# 5DPD8_v1_0_OS_Sheet3.net
KiCad netlist of a schematic drawn in Altium Designer
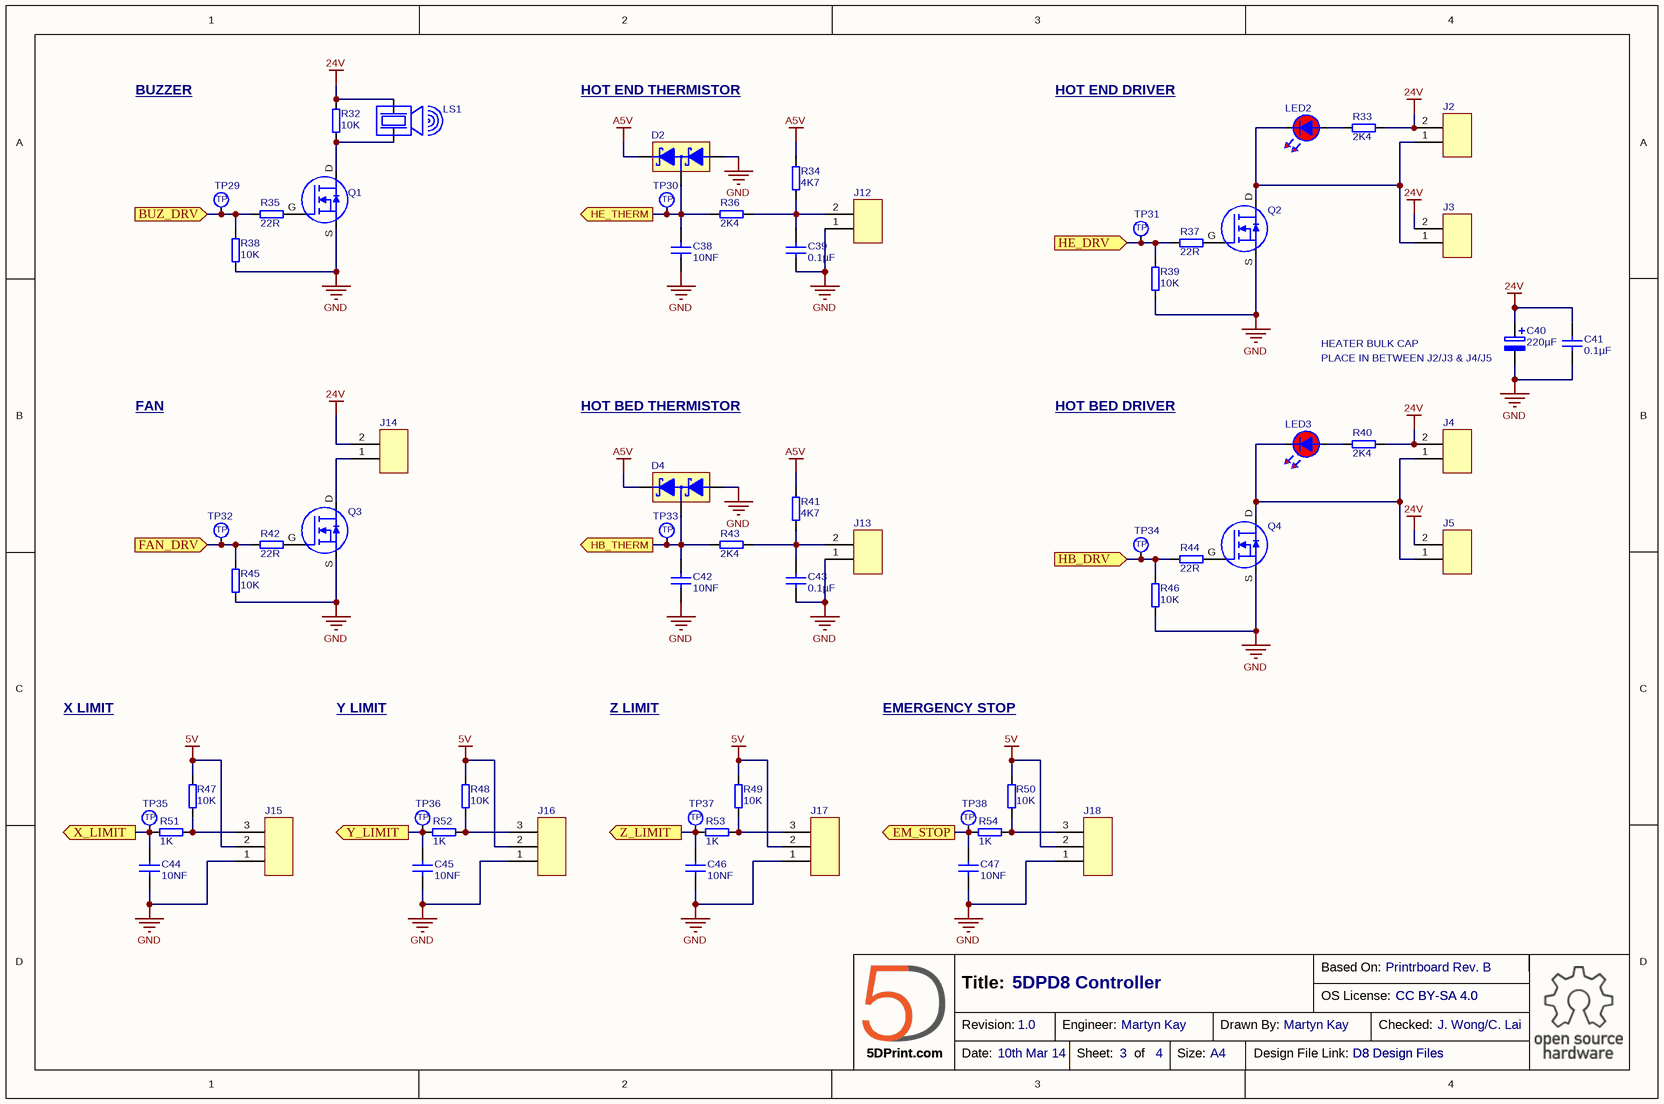
[diagram p0: 5DPD8_v1.0_OS_Sheet3.SchDoc]

(export (version "E")
  (design (tool "Eeschema 10.0.6"))
  (components
    (comp (ref "C38")
      (value "10NF")
      (footprint "CAPC0603(1608)100_N")
      (description "CAP CER 10000PF 50V 10% X7R 0603")
      (fields
        (field (name "MANUFACTURER") "Yageo")
        (field (name "MANUFACTURERPARTNUMBER") "CC0603KPX7R9BB103")
      )
      (libsource (lib "5DPD8") (part "C0603-10NF-50V-10%-X7R"))
    )
    (comp (ref "C39")
      (value "0.1µF")
      (footprint "CAPC0603(1608)100_N")
      (description "CAP CER 0.1UF 50V 10% X7R 0603")
      (fields
        (field (name "MANUFACTURER") "Yageo")
        (field (name "MANUFACTURERPARTNUMBER") "CC0603KRX7R9BB104")
      )
      (libsource (lib "5DPD8") (part "C0603-0.1UF-50V-10%-X7R"))
    )
    (comp (ref "C40")
      (value "220µF")
      (footprint "CAPRAD8X11.5")
      (description "CAP ALUM 220UF 35V 20% RADIAL")
      (fields
        (field (name "MANUFACTURER") "Rubycon")
        (field (name "MANUFACTURERPARTNUMBER") "35ZLH220MEFC8X11.5")
      )
      (libsource (lib "5DPD8") (part "CAP_RAD-ALU-220UF-35V-20%"))
    )
    (comp (ref "C41")
      (value "0.1µF")
      (footprint "CAPC0603(1608)100_N")
      (description "CAP CER 0.1UF 50V 10% X7R 0603")
      (fields
        (field (name "MANUFACTURER") "Yageo")
        (field (name "MANUFACTURERPARTNUMBER") "CC0603KRX7R9BB104")
      )
      (libsource (lib "5DPD8") (part "C0603-0.1UF-50V-10%-X7R"))
    )
    (comp (ref "C42")
      (value "10NF")
      (footprint "CAPC0603(1608)100_N")
      (description "CAP CER 10000PF 50V 10% X7R 0603")
      (fields
        (field (name "MANUFACTURER") "Yageo")
        (field (name "MANUFACTURERPARTNUMBER") "CC0603KPX7R9BB103")
      )
      (libsource (lib "5DPD8") (part "C0603-10NF-50V-10%-X7R"))
    )
    (comp (ref "C43")
      (value "0.1µF")
      (footprint "CAPC0603(1608)100_N")
      (description "CAP CER 0.1UF 50V 10% X7R 0603")
      (fields
        (field (name "MANUFACTURER") "Yageo")
        (field (name "MANUFACTURERPARTNUMBER") "CC0603KRX7R9BB104")
      )
      (libsource (lib "5DPD8") (part "C0603-0.1UF-50V-10%-X7R"))
    )
    (comp (ref "C44")
      (value "10NF")
      (footprint "CAPC0603(1608)100_N")
      (description "CAP CER 10000PF 50V 10% X7R 0603")
      (fields
        (field (name "MANUFACTURER") "Yageo")
        (field (name "MANUFACTURERPARTNUMBER") "CC0603KPX7R9BB103")
      )
      (libsource (lib "5DPD8") (part "C0603-10NF-50V-10%-X7R"))
    )
    (comp (ref "C45")
      (value "10NF")
      (footprint "CAPC0603(1608)100_N")
      (description "CAP CER 10000PF 50V 10% X7R 0603")
      (fields
        (field (name "MANUFACTURER") "Yageo")
        (field (name "MANUFACTURERPARTNUMBER") "CC0603KPX7R9BB103")
      )
      (libsource (lib "5DPD8") (part "C0603-10NF-50V-10%-X7R"))
    )
    (comp (ref "C46")
      (value "10NF")
      (footprint "CAPC0603(1608)100_N")
      (description "CAP CER 10000PF 50V 10% X7R 0603")
      (fields
        (field (name "MANUFACTURER") "Yageo")
        (field (name "MANUFACTURERPARTNUMBER") "CC0603KPX7R9BB103")
      )
      (libsource (lib "5DPD8") (part "C0603-10NF-50V-10%-X7R"))
    )
    (comp (ref "C47")
      (value "10NF")
      (footprint "CAPC0603(1608)100_N")
      (description "CAP CER 10000PF 50V 10% X7R 0603")
      (fields
        (field (name "MANUFACTURER") "Yageo")
        (field (name "MANUFACTURERPARTNUMBER") "CC0603KPX7R9BB103")
      )
      (libsource (lib "5DPD8") (part "C0603-10NF-50V-10%-X7R"))
    )
    (comp (ref "D2")
      (value "BAT54S,215")
      (footprint "SOT95P237X112-3N")
      (description "DIODE SCHOTTKY 30V 200MA TO236AB")
      (fields (field (name "MANUFACTURER") "NXP Semiconductors"))
      (libsource (lib "5DPD8") (part "DIO_BAT54S,215"))
    )
    (comp (ref "D4")
      (value "BAT54S,215")
      (footprint "SOT95P237X112-3N")
      (description "DIODE SCHOTTKY 30V 200MA TO236AB")
      (fields (field (name "MANUFACTURER") "NXP Semiconductors"))
      (libsource (lib "5DPD8") (part "DIO_BAT54S,215"))
    )
    (comp (ref "J2")
      (value "0039281023")
      (footprint "MOLEX_39-28-1023")
      (description "CONN HEADER 2POS 4.2MM VERT TIN")
      (fields (field (name "MANUFACTURER") "Molex Inc"))
      (libsource (lib "5DPD8") (part "CON_MLX_39-28-1023"))
    )
    (comp (ref "J3")
      (value "0039281023")
      (footprint "MOLEX_39-28-1023")
      (description "CONN HEADER 2POS 4.2MM VERT TIN")
      (fields (field (name "MANUFACTURER") "Molex Inc"))
      (libsource (lib "5DPD8") (part "CON_MLX_39-28-1023"))
    )
    (comp (ref "J4")
      (value "0039281023")
      (footprint "MOLEX_39-28-1023")
      (description "CONN HEADER 2POS 4.2MM VERT TIN")
      (fields (field (name "MANUFACTURER") "Molex Inc"))
      (libsource (lib "5DPD8") (part "CON_MLX_39-28-1023"))
    )
    (comp (ref "J5")
      (value "0039281023")
      (footprint "MOLEX_39-28-1023")
      (description "CONN HEADER 2POS 4.2MM VERT TIN")
      (fields (field (name "MANUFACTURER") "Molex Inc"))
      (libsource (lib "5DPD8") (part "CON_MLX_39-28-1023"))
    )
    (comp (ref "J12")
      (value "0022272021")
      (footprint "MOLEX_22-27-2021")
      (description "CONN HEADER 2POS .100 VERT TIN")
      (fields (field (name "MANUFACTURER") "Molex Inc"))
      (libsource (lib "5DPD8") (part "CON_MLX_22-27-2021"))
    )
    (comp (ref "J13")
      (value "0022272021")
      (footprint "MOLEX_22-27-2021")
      (description "CONN HEADER 2POS .100 VERT TIN")
      (fields (field (name "MANUFACTURER") "Molex Inc"))
      (libsource (lib "5DPD8") (part "CON_MLX_22-27-2021"))
    )
    (comp (ref "J14")
      (value "0022272021")
      (footprint "MOLEX_22-27-2021")
      (description "CONN HEADER 2POS .100 VERT TIN")
      (fields (field (name "MANUFACTURER") "Molex Inc"))
      (libsource (lib "5DPD8") (part "CON_MLX_22-27-2021"))
    )
    (comp (ref "J15")
      (value "0022272031")
      (footprint "MOLEX_22-27-2031")
      (description "CONN HEADER 3POS .100 VERT TIN")
      (fields (field (name "MANUFACTURER") "Molex Inc"))
      (libsource (lib "5DPD8") (part "CON_MLX_22-27-2031"))
    )
    (comp (ref "J16")
      (value "0022272031")
      (footprint "MOLEX_22-27-2031")
      (description "CONN HEADER 3POS .100 VERT TIN")
      (fields (field (name "MANUFACTURER") "Molex Inc"))
      (libsource (lib "5DPD8") (part "CON_MLX_22-27-2031"))
    )
    (comp (ref "J17")
      (value "0022272031")
      (footprint "MOLEX_22-27-2031")
      (description "CONN HEADER 3POS .100 VERT TIN")
      (fields (field (name "MANUFACTURER") "Molex Inc"))
      (libsource (lib "5DPD8") (part "CON_MLX_22-27-2031"))
    )
    (comp (ref "J18")
      (value "0022272031")
      (footprint "MOLEX_22-27-2031")
      (description "CONN HEADER 3POS .100 VERT TIN")
      (fields (field (name "MANUFACTURER") "Molex Inc"))
      (libsource (lib "5DPD8") (part "CON_MLX_22-27-2031"))
    )
    (comp (ref "LED2")
      (value "HSMH-C190")
      (footprint "LEDC0603(1608)_N-RED")
      (description "LED 660NM RED DIFF 0603 SMD")
      (fields (field (name "MANUFACTURER") "Avago Technologies US Inc."))
      (libsource (lib "5DPD8") (part "LED_HSMH-C190"))
    )
    (comp (ref "LED3")
      (value "HSMH-C190")
      (footprint "LEDC0603(1608)_N-RED")
      (description "LED 660NM RED DIFF 0603 SMD")
      (fields (field (name "MANUFACTURER") "Avago Technologies US Inc."))
      (libsource (lib "5DPD8") (part "LED_HSMH-C190"))
    )
    (comp (ref "LS1")
      (value "PS1740P02E")
      (footprint "PS17")
      (description "BUZZER PIEZO 4KHZ 17MM PC MOUNT")
      (fields (field (name "MANUFACTURER") "TDK Corporation"))
      (libsource (lib "5DPD8") (part "LS_PS1740P02E"))
    )
    (comp (ref "Q1")
      (value "2N7002,215")
      (footprint "SOT95P237X112-3N-GSD")
      (description "MOSFET N-CH 60V 300MA SOT-23")
      (fields (field (name "MANUFACTURER") "NXP Semiconductors"))
      (libsource (lib "5DPD8") (part "FET_2N7002,215"))
    )
    (comp (ref "Q2")
      (value "PSMN9R5-30YLC,115")
      (footprint "SOT669(LFPAK56)")
      (description "MOSFET N-CH 30V 44A LL LFPAK")
      (fields (field (name "MANUFACTURER") "NXP Semiconductors"))
      (libsource (lib "5DPD8") (part "FET_PSMN9R5-30YLC,115"))
    )
    (comp (ref "Q3")
      (value "IRLML2060TRPBF")
      (footprint "SOT95P237X112-3N-GSD")
      (description "MOSFET N-CH 60V 1.2A SOT23-3")
      (fields (field (name "MANUFACTURER") "International Rectifier"))
      (libsource (lib "5DPD8") (part "FET_IRLML2060TRPBF"))
    )
    (comp (ref "Q4")
      (value "PSMN9R5-30YLC,115")
      (footprint "SOT669(LFPAK56)")
      (description "MOSFET N-CH 30V 44A LL LFPAK")
      (fields (field (name "MANUFACTURER") "NXP Semiconductors"))
      (libsource (lib "5DPD8") (part "FET_PSMN9R5-30YLC,115"))
    )
    (comp (ref "R32")
      (value "10K")
      (footprint "RESC0603(1608)_N")
      (description "RES 10K OHM 1/10W 5% 0603 SMD")
      (fields (field (name "MANUFACTURER") "Yageo") (field (name "MANUFACTURERPARTNUMBER") "RC0603JR-0710KL"))
      (libsource (lib "5DPD8") (part "R0603-10K-0.1W-5%"))
    )
    (comp (ref "R33")
      (value "2K4")
      (footprint "RESC0603(1608)_N")
      (description "RES 2.4K OHM 1/4W 5% 0603 SMD")
      (fields
        (field (name "MANUFACTURER") "Rohm Semiconductor")
        (field (name "MANUFACTURERPARTNUMBER") "ESR03EZPJ242")
      )
      (libsource (lib "5DPD8") (part "R0603-2K4-0.25W-5%"))
    )
    (comp (ref "R34")
      (value "4K7")
      (footprint "RESC0603(1608)_N")
      (description "RES 4.70K OHM 1/10W 1% 0603 SMD")
      (fields (field (name "MANUFACTURER") "Yageo") (field (name "MANUFACTURERPARTNUMBER") "RC0603FR-074K7L"))
      (libsource (lib "5DPD8") (part "R0603-4K7-0.1W-1%"))
    )
    (comp (ref "R35")
      (value "22R")
      (footprint "RESC0603(1608)_N")
      (description "RES 22.0 OHM 1/10W 1% 0603 SMD")
      (fields (field (name "MANUFACTURER") "Yageo") (field (name "MANUFACTURERPARTNUMBER") "RC0603FR-0722RL"))
      (libsource (lib "5DPD8") (part "R0603-22R-0.1W-1%"))
    )
    (comp (ref "R36")
      (value "2K4")
      (footprint "RESC0603(1608)_N")
      (description "RES 2.4K OHM 1/4W 5% 0603 SMD")
      (fields
        (field (name "MANUFACTURER") "Rohm Semiconductor")
        (field (name "MANUFACTURERPARTNUMBER") "ESR03EZPJ242")
      )
      (libsource (lib "5DPD8") (part "R0603-2K4-0.25W-5%"))
    )
    (comp (ref "R37")
      (value "22R")
      (footprint "RESC0603(1608)_N")
      (description "RES 22.0 OHM 1/10W 1% 0603 SMD")
      (fields (field (name "MANUFACTURER") "Yageo") (field (name "MANUFACTURERPARTNUMBER") "RC0603FR-0722RL"))
      (libsource (lib "5DPD8") (part "R0603-22R-0.1W-1%"))
    )
    (comp (ref "R38")
      (value "10K")
      (footprint "RESC0603(1608)_N")
      (description "RES 10K OHM 1/10W 5% 0603 SMD")
      (fields (field (name "MANUFACTURER") "Yageo") (field (name "MANUFACTURERPARTNUMBER") "RC0603JR-0710KL"))
      (libsource (lib "5DPD8") (part "R0603-10K-0.1W-5%"))
    )
    (comp (ref "R39")
      (value "10K")
      (footprint "RESC0603(1608)_N")
      (description "RES 10K OHM 1/10W 5% 0603 SMD")
      (fields (field (name "MANUFACTURER") "Yageo") (field (name "MANUFACTURERPARTNUMBER") "RC0603JR-0710KL"))
      (libsource (lib "5DPD8") (part "R0603-10K-0.1W-5%"))
    )
    (comp (ref "R40")
      (value "2K4")
      (footprint "RESC0603(1608)_N")
      (description "RES 2.4K OHM 1/4W 5% 0603 SMD")
      (fields
        (field (name "MANUFACTURER") "Rohm Semiconductor")
        (field (name "MANUFACTURERPARTNUMBER") "ESR03EZPJ242")
      )
      (libsource (lib "5DPD8") (part "R0603-2K4-0.25W-5%"))
    )
    (comp (ref "R41")
      (value "4K7")
      (footprint "RESC0603(1608)_N")
      (description "RES 4.70K OHM 1/10W 1% 0603 SMD")
      (fields (field (name "MANUFACTURER") "Yageo") (field (name "MANUFACTURERPARTNUMBER") "RC0603FR-074K7L"))
      (libsource (lib "5DPD8") (part "R0603-4K7-0.1W-1%"))
    )
    (comp (ref "R42")
      (value "22R")
      (footprint "RESC0603(1608)_N")
      (description "RES 22.0 OHM 1/10W 1% 0603 SMD")
      (fields (field (name "MANUFACTURER") "Yageo") (field (name "MANUFACTURERPARTNUMBER") "RC0603FR-0722RL"))
      (libsource (lib "5DPD8") (part "R0603-22R-0.1W-1%"))
    )
    (comp (ref "R43")
      (value "2K4")
      (footprint "RESC0603(1608)_N")
      (description "RES 2.4K OHM 1/4W 5% 0603 SMD")
      (fields
        (field (name "MANUFACTURER") "Rohm Semiconductor")
        (field (name "MANUFACTURERPARTNUMBER") "ESR03EZPJ242")
      )
      (libsource (lib "5DPD8") (part "R0603-2K4-0.25W-5%"))
    )
    (comp (ref "R44")
      (value "22R")
      (footprint "RESC0603(1608)_N")
      (description "RES 22.0 OHM 1/10W 1% 0603 SMD")
      (fields (field (name "MANUFACTURER") "Yageo") (field (name "MANUFACTURERPARTNUMBER") "RC0603FR-0722RL"))
      (libsource (lib "5DPD8") (part "R0603-22R-0.1W-1%"))
    )
    (comp (ref "R45")
      (value "10K")
      (footprint "RESC0603(1608)_N")
      (description "RES 10K OHM 1/10W 5% 0603 SMD")
      (fields (field (name "MANUFACTURER") "Yageo") (field (name "MANUFACTURERPARTNUMBER") "RC0603JR-0710KL"))
      (libsource (lib "5DPD8") (part "R0603-10K-0.1W-5%"))
    )
    (comp (ref "R46")
      (value "10K")
      (footprint "RESC0603(1608)_N")
      (description "RES 10K OHM 1/10W 5% 0603 SMD")
      (fields (field (name "MANUFACTURER") "Yageo") (field (name "MANUFACTURERPARTNUMBER") "RC0603JR-0710KL"))
      (libsource (lib "5DPD8") (part "R0603-10K-0.1W-5%"))
    )
    (comp (ref "R47")
      (value "10K")
      (footprint "RESC0603(1608)_N")
      (description "RES 10K OHM 1/10W 5% 0603 SMD")
      (fields (field (name "MANUFACTURER") "Yageo") (field (name "MANUFACTURERPARTNUMBER") "RC0603JR-0710KL"))
      (libsource (lib "5DPD8") (part "R0603-10K-0.1W-5%"))
    )
    (comp (ref "R48")
      (value "10K")
      (footprint "RESC0603(1608)_N")
      (description "RES 10K OHM 1/10W 5% 0603 SMD")
      (fields (field (name "MANUFACTURER") "Yageo") (field (name "MANUFACTURERPARTNUMBER") "RC0603JR-0710KL"))
      (libsource (lib "5DPD8") (part "R0603-10K-0.1W-5%"))
    )
    (comp (ref "R49")
      (value "10K")
      (footprint "RESC0603(1608)_N")
      (description "RES 10K OHM 1/10W 5% 0603 SMD")
      (fields (field (name "MANUFACTURER") "Yageo") (field (name "MANUFACTURERPARTNUMBER") "RC0603JR-0710KL"))
      (libsource (lib "5DPD8") (part "R0603-10K-0.1W-5%"))
    )
    (comp (ref "R50")
      (value "10K")
      (footprint "RESC0603(1608)_N")
      (description "RES 10K OHM 1/10W 5% 0603 SMD")
      (fields (field (name "MANUFACTURER") "Yageo") (field (name "MANUFACTURERPARTNUMBER") "RC0603JR-0710KL"))
      (libsource (lib "5DPD8") (part "R0603-10K-0.1W-5%"))
    )
    (comp (ref "R51")
      (value "1K")
      (footprint "RESC0603(1608)_N")
      (description "RES 1.00K OHM 1/10W 1% 0603 SMD")
      (fields (field (name "MANUFACTURER") "Yageo") (field (name "MANUFACTURERPARTNUMBER") "RC0603FR-071KL"))
      (libsource (lib "5DPD8") (part "R0603-1K-0.1W-1%"))
    )
    (comp (ref "R52")
      (value "1K")
      (footprint "RESC0603(1608)_N")
      (description "RES 1.00K OHM 1/10W 1% 0603 SMD")
      (fields (field (name "MANUFACTURER") "Yageo") (field (name "MANUFACTURERPARTNUMBER") "RC0603FR-071KL"))
      (libsource (lib "5DPD8") (part "R0603-1K-0.1W-1%"))
    )
    (comp (ref "R53")
      (value "1K")
      (footprint "RESC0603(1608)_N")
      (description "RES 1.00K OHM 1/10W 1% 0603 SMD")
      (fields (field (name "MANUFACTURER") "Yageo") (field (name "MANUFACTURERPARTNUMBER") "RC0603FR-071KL"))
      (libsource (lib "5DPD8") (part "R0603-1K-0.1W-1%"))
    )
    (comp (ref "R54")
      (value "1K")
      (footprint "RESC0603(1608)_N")
      (description "RES 1.00K OHM 1/10W 1% 0603 SMD")
      (fields (field (name "MANUFACTURER") "Yageo") (field (name "MANUFACTURERPARTNUMBER") "RC0603FR-071KL"))
      (libsource (lib "5DPD8") (part "R0603-1K-0.1W-1%"))
    )
    (comp (ref "TP29")
      (value "TESTPOINT")
      (footprint "TESTPOINT")
      (libsource (lib "5DPD8") (part "TESTPOINT"))
    )
    (comp (ref "TP30")
      (value "TESTPOINT")
      (footprint "TESTPOINT")
      (libsource (lib "5DPD8") (part "TESTPOINT"))
    )
    (comp (ref "TP31")
      (value "TESTPOINT")
      (footprint "TESTPOINT")
      (libsource (lib "5DPD8") (part "TESTPOINT"))
    )
    (comp (ref "TP32")
      (value "TESTPOINT")
      (footprint "TESTPOINT")
      (libsource (lib "5DPD8") (part "TESTPOINT"))
    )
    (comp (ref "TP33")
      (value "TESTPOINT")
      (footprint "TESTPOINT")
      (libsource (lib "5DPD8") (part "TESTPOINT"))
    )
    (comp (ref "TP34")
      (value "TESTPOINT")
      (footprint "TESTPOINT")
      (libsource (lib "5DPD8") (part "TESTPOINT"))
    )
    (comp (ref "TP35")
      (value "TESTPOINT")
      (footprint "TESTPOINT")
      (libsource (lib "5DPD8") (part "TESTPOINT"))
    )
    (comp (ref "TP36")
      (value "TESTPOINT")
      (footprint "TESTPOINT")
      (libsource (lib "5DPD8") (part "TESTPOINT"))
    )
    (comp (ref "TP37")
      (value "TESTPOINT")
      (footprint "TESTPOINT")
      (libsource (lib "5DPD8") (part "TESTPOINT"))
    )
    (comp (ref "TP38")
      (value "TESTPOINT")
      (footprint "TESTPOINT")
      (libsource (lib "5DPD8") (part "TESTPOINT"))
    )
  )
  (nets
    (net (code "1") (name "/BUZ_DRV") (class "Default")
      (node (ref "R35") (pin "1") (pinfunction "1_1") (pintype "passive"))
      (node (ref "R38") (pin "2") (pinfunction "2_2") (pintype "passive"))
      (node (ref "TP29") (pin "1") (pinfunction "1_1") (pintype "passive"))
    )
    (net (code "2") (name "/EM_STOP") (class "Default")
      (node (ref "C47") (pin "2") (pinfunction "2_2") (pintype "passive"))
      (node (ref "R54") (pin "1") (pinfunction "1_1") (pintype "passive"))
      (node (ref "TP38") (pin "1") (pinfunction "1_1") (pintype "passive"))
    )
    (net (code "3") (name "/FAN_DRV") (class "Default")
      (node (ref "R42") (pin "1") (pinfunction "1_1") (pintype "passive"))
      (node (ref "R45") (pin "2") (pinfunction "2_2") (pintype "passive"))
      (node (ref "TP32") (pin "1") (pinfunction "1_1") (pintype "passive"))
    )
    (net (code "4") (name "/HB_DRV") (class "Default")
      (node (ref "R44") (pin "1") (pinfunction "1_1") (pintype "passive"))
      (node (ref "R46") (pin "2") (pinfunction "2_2") (pintype "passive"))
      (node (ref "TP34") (pin "1") (pinfunction "1_1") (pintype "passive"))
    )
    (net (code "5") (name "/HB_THERM") (class "Default")
      (node (ref "C42") (pin "2") (pinfunction "2_2") (pintype "passive"))
      (node (ref "D4") (pin "3") (pinfunction "3_3") (pintype "passive"))
      (node (ref "R43") (pin "1") (pinfunction "1_1") (pintype "passive"))
      (node (ref "TP33") (pin "1") (pinfunction "1_1") (pintype "passive"))
    )
    (net (code "6") (name "/HE_DRV") (class "Default")
      (node (ref "R37") (pin "1") (pinfunction "1_1") (pintype "passive"))
      (node (ref "R39") (pin "2") (pinfunction "2_2") (pintype "passive"))
      (node (ref "TP31") (pin "1") (pinfunction "1_1") (pintype "passive"))
    )
    (net (code "7") (name "/HE_THERM") (class "Default")
      (node (ref "C38") (pin "2") (pinfunction "2_2") (pintype "passive"))
      (node (ref "D2") (pin "3") (pinfunction "3_3") (pintype "passive"))
      (node (ref "R36") (pin "1") (pinfunction "1_1") (pintype "passive"))
      (node (ref "TP30") (pin "1") (pinfunction "1_1") (pintype "passive"))
    )
    (net (code "8") (name "/X_LIMIT") (class "Default")
      (node (ref "C44") (pin "2") (pinfunction "2_2") (pintype "passive"))
      (node (ref "R51") (pin "1") (pinfunction "1_1") (pintype "passive"))
      (node (ref "TP35") (pin "1") (pinfunction "1_1") (pintype "passive"))
    )
    (net (code "9") (name "/Y_LIMIT") (class "Default")
      (node (ref "C45") (pin "2") (pinfunction "2_2") (pintype "passive"))
      (node (ref "R52") (pin "1") (pinfunction "1_1") (pintype "passive"))
      (node (ref "TP36") (pin "1") (pinfunction "1_1") (pintype "passive"))
    )
    (net (code "10") (name "/Z_LIMIT") (class "Default")
      (node (ref "C46") (pin "2") (pinfunction "2_2") (pintype "passive"))
      (node (ref "R53") (pin "1") (pinfunction "1_1") (pintype "passive"))
      (node (ref "TP37") (pin "1") (pinfunction "1_1") (pintype "passive"))
    )
    (net (code "11") (name "5V") (class "Default")
      (node (ref "J15") (pin "2") (pinfunction "2_2") (pintype "passive"))
      (node (ref "J16") (pin "2") (pinfunction "2_2") (pintype "passive"))
      (node (ref "J17") (pin "2") (pinfunction "2_2") (pintype "passive"))
      (node (ref "J18") (pin "2") (pinfunction "2_2") (pintype "passive"))
      (node (ref "R47") (pin "2") (pinfunction "2_2") (pintype "passive"))
      (node (ref "R48") (pin "2") (pinfunction "2_2") (pintype "passive"))
      (node (ref "R49") (pin "2") (pinfunction "2_2") (pintype "passive"))
      (node (ref "R50") (pin "2") (pinfunction "2_2") (pintype "passive"))
    )
    (net (code "12") (name "24V") (class "Default")
      (node (ref "C40") (pin "1") (pinfunction "+_1") (pintype "passive"))
      (node (ref "C41") (pin "2") (pinfunction "2_2") (pintype "passive"))
      (node (ref "J14") (pin "2") (pinfunction "2_2") (pintype "passive"))
      (node (ref "J2") (pin "2") (pinfunction "2_2") (pintype "passive"))
      (node (ref "J3") (pin "2") (pinfunction "2_2") (pintype "passive"))
      (node (ref "J4") (pin "2") (pinfunction "2_2") (pintype "passive"))
      (node (ref "J5") (pin "2") (pinfunction "2_2") (pintype "passive"))
      (node (ref "LS1") (pin "2") (pinfunction "2_2") (pintype "passive"))
      (node (ref "R32") (pin "2") (pinfunction "2_2") (pintype "passive"))
      (node (ref "R33") (pin "2") (pinfunction "2_2") (pintype "passive"))
      (node (ref "R40") (pin "2") (pinfunction "2_2") (pintype "passive"))
    )
    (net (code "13") (name "A5V") (class "Default")
      (node (ref "D2") (pin "2") (pinfunction "2_2") (pintype "passive"))
      (node (ref "D4") (pin "2") (pinfunction "2_2") (pintype "passive"))
      (node (ref "R34") (pin "2") (pinfunction "2_2") (pintype "passive"))
      (node (ref "R41") (pin "2") (pinfunction "2_2") (pintype "passive"))
    )
    (net (code "14") (name "GND") (class "Default")
      (node (ref "C38") (pin "1") (pinfunction "1_1") (pintype "passive"))
      (node (ref "C39") (pin "1") (pinfunction "1_1") (pintype "passive"))
      (node (ref "C40") (pin "2") (pinfunction "-_2") (pintype "passive"))
      (node (ref "C41") (pin "1") (pinfunction "1_1") (pintype "passive"))
      (node (ref "C42") (pin "1") (pinfunction "1_1") (pintype "passive"))
      (node (ref "C43") (pin "1") (pinfunction "1_1") (pintype "passive"))
      (node (ref "C44") (pin "1") (pinfunction "1_1") (pintype "passive"))
      (node (ref "C45") (pin "1") (pinfunction "1_1") (pintype "passive"))
      (node (ref "C46") (pin "1") (pinfunction "1_1") (pintype "passive"))
      (node (ref "C47") (pin "1") (pinfunction "1_1") (pintype "passive"))
      (node (ref "D2") (pin "1") (pinfunction "1_1") (pintype "passive"))
      (node (ref "D4") (pin "1") (pinfunction "1_1") (pintype "passive"))
      (node (ref "J12") (pin "1") (pinfunction "1_1") (pintype "passive"))
      (node (ref "J13") (pin "1") (pinfunction "1_1") (pintype "passive"))
      (node (ref "J15") (pin "1") (pinfunction "1_1") (pintype "passive"))
      (node (ref "J16") (pin "1") (pinfunction "1_1") (pintype "passive"))
      (node (ref "J17") (pin "1") (pinfunction "1_1") (pintype "passive"))
      (node (ref "J18") (pin "1") (pinfunction "1_1") (pintype "passive"))
      (node (ref "Q1") (pin "S") (pinfunction "S_S") (pintype "passive"))
      (node (ref "Q2") (pin "S") (pinfunction "S_S") (pintype "passive"))
      (node (ref "Q3") (pin "S") (pinfunction "S_S") (pintype "passive"))
      (node (ref "Q4") (pin "S") (pinfunction "S_S") (pintype "passive"))
      (node (ref "R38") (pin "1") (pinfunction "1_1") (pintype "passive"))
      (node (ref "R39") (pin "1") (pinfunction "1_1") (pintype "passive"))
      (node (ref "R45") (pin "1") (pinfunction "1_1") (pintype "passive"))
      (node (ref "R46") (pin "1") (pinfunction "1_1") (pintype "passive"))
    )
    (net (code "15") (name "Net-(C39-Pad2)") (class "Default")
      (node (ref "C39") (pin "2") (pinfunction "2_2") (pintype "passive"))
      (node (ref "J12") (pin "2") (pinfunction "2_2") (pintype "passive"))
      (node (ref "R34") (pin "1") (pinfunction "1_1") (pintype "passive"))
      (node (ref "R36") (pin "2") (pinfunction "2_2") (pintype "passive"))
    )
    (net (code "16") (name "Net-(C43-Pad2)") (class "Default")
      (node (ref "C43") (pin "2") (pinfunction "2_2") (pintype "passive"))
      (node (ref "J13") (pin "2") (pinfunction "2_2") (pintype "passive"))
      (node (ref "R41") (pin "1") (pinfunction "1_1") (pintype "passive"))
      (node (ref "R43") (pin "2") (pinfunction "2_2") (pintype "passive"))
    )
    (net (code "17") (name "Net-(J2-Pad1)") (class "Default")
      (node (ref "J2") (pin "1") (pinfunction "1_1") (pintype "passive"))
      (node (ref "J3") (pin "1") (pinfunction "1_1") (pintype "passive"))
      (node (ref "LED2") (pin "K") (pinfunction "K_K") (pintype "passive"))
      (node (ref "Q2") (pin "D") (pinfunction "D_D") (pintype "passive"))
    )
    (net (code "18") (name "Net-(J4-Pad1)") (class "Default")
      (node (ref "J4") (pin "1") (pinfunction "1_1") (pintype "passive"))
      (node (ref "J5") (pin "1") (pinfunction "1_1") (pintype "passive"))
      (node (ref "LED3") (pin "K") (pinfunction "K_K") (pintype "passive"))
      (node (ref "Q4") (pin "D") (pinfunction "D_D") (pintype "passive"))
    )
    (net (code "19") (name "Net-(J14-Pad1)") (class "Default")
      (node (ref "J14") (pin "1") (pinfunction "1_1") (pintype "passive"))
      (node (ref "Q3") (pin "D") (pinfunction "D_D") (pintype "passive"))
    )
    (net (code "20") (name "Net-(J15-Pad3)") (class "Default")
      (node (ref "J15") (pin "3") (pinfunction "3_3") (pintype "passive"))
      (node (ref "R47") (pin "1") (pinfunction "1_1") (pintype "passive"))
      (node (ref "R51") (pin "2") (pinfunction "2_2") (pintype "passive"))
    )
    (net (code "21") (name "Net-(J16-Pad3)") (class "Default")
      (node (ref "J16") (pin "3") (pinfunction "3_3") (pintype "passive"))
      (node (ref "R48") (pin "1") (pinfunction "1_1") (pintype "passive"))
      (node (ref "R52") (pin "2") (pinfunction "2_2") (pintype "passive"))
    )
    (net (code "22") (name "Net-(J17-Pad3)") (class "Default")
      (node (ref "J17") (pin "3") (pinfunction "3_3") (pintype "passive"))
      (node (ref "R49") (pin "1") (pinfunction "1_1") (pintype "passive"))
      (node (ref "R53") (pin "2") (pinfunction "2_2") (pintype "passive"))
    )
    (net (code "23") (name "Net-(J18-Pad3)") (class "Default")
      (node (ref "J18") (pin "3") (pinfunction "3_3") (pintype "passive"))
      (node (ref "R50") (pin "1") (pinfunction "1_1") (pintype "passive"))
      (node (ref "R54") (pin "2") (pinfunction "2_2") (pintype "passive"))
    )
    (net (code "24") (name "Net-(LED2-PadA)") (class "Default")
      (node (ref "LED2") (pin "A") (pinfunction "A_A") (pintype "passive"))
      (node (ref "R33") (pin "1") (pinfunction "1_1") (pintype "passive"))
    )
    (net (code "25") (name "Net-(LED3-PadA)") (class "Default")
      (node (ref "LED3") (pin "A") (pinfunction "A_A") (pintype "passive"))
      (node (ref "R40") (pin "1") (pinfunction "1_1") (pintype "passive"))
    )
    (net (code "26") (name "Net-(LS1-Pad1)") (class "Default")
      (node (ref "LS1") (pin "1") (pinfunction "1_1") (pintype "passive"))
      (node (ref "Q1") (pin "D") (pinfunction "D_D") (pintype "passive"))
      (node (ref "R32") (pin "1") (pinfunction "1_1") (pintype "passive"))
    )
    (net (code "27") (name "Net-(Q1-PadG)") (class "Default")
      (node (ref "Q1") (pin "G") (pinfunction "G_G") (pintype "passive"))
      (node (ref "R35") (pin "2") (pinfunction "2_2") (pintype "passive"))
    )
    (net (code "28") (name "Net-(Q2-PadG)") (class "Default")
      (node (ref "Q2") (pin "G") (pinfunction "G_G") (pintype "passive"))
      (node (ref "R37") (pin "2") (pinfunction "2_2") (pintype "passive"))
    )
    (net (code "29") (name "Net-(Q3-PadG)") (class "Default")
      (node (ref "Q3") (pin "G") (pinfunction "G_G") (pintype "passive"))
      (node (ref "R42") (pin "2") (pinfunction "2_2") (pintype "passive"))
    )
    (net (code "30") (name "Net-(Q4-PadG)") (class "Default")
      (node (ref "Q4") (pin "G") (pinfunction "G_G") (pintype "passive"))
      (node (ref "R44") (pin "2") (pinfunction "2_2") (pintype "passive"))
    )
  )
)
